# 5_CLOCK_GENERATOR.net
KiCad netlist of a schematic drawn in Altium Designer
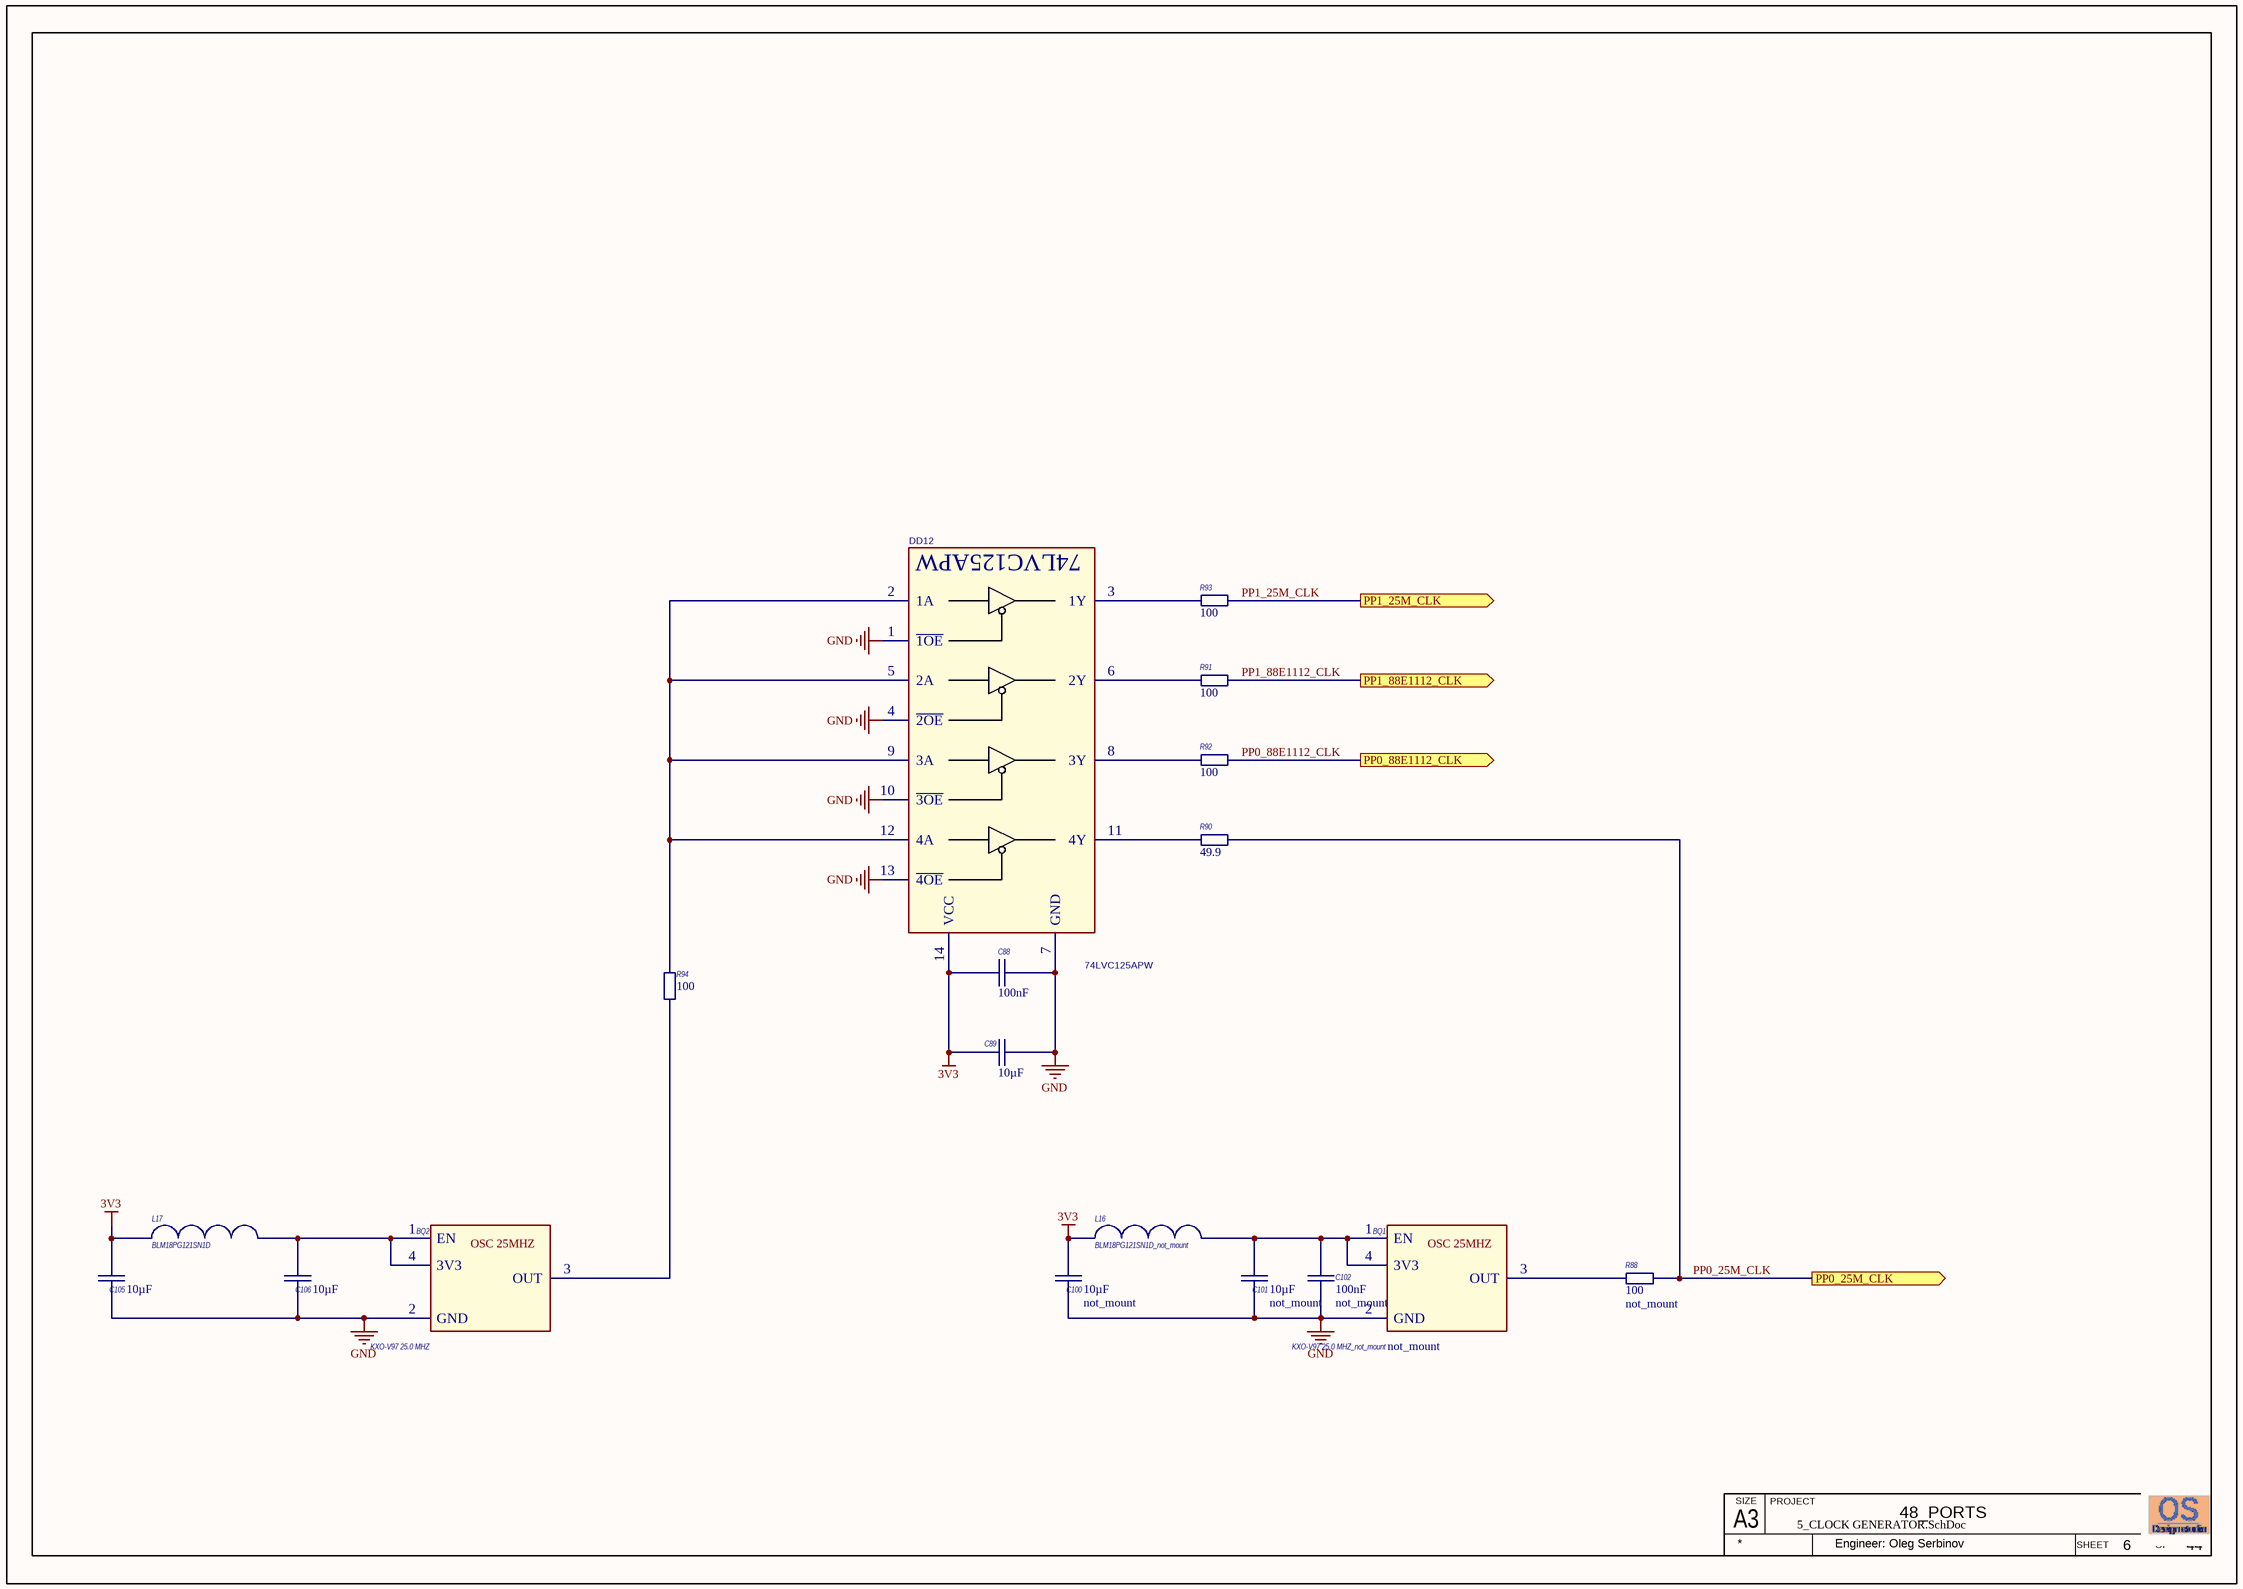
[diagram p0: 5_CLOCK GENERATOR.SchDoc]

(export (version "E")
  (design (tool "Eeschema 10.0.6"))
  (components
    (comp (ref "BQ1")
      (value "KXO-V97 25.0 MHZ_not_mount")
      (footprint "KXO-V97")
      (description "Oscillator 25MHZ 3.3V HCMOS SMT_not_mount")
      (fields
        (field (name "MANUFACTURER") "EYER ELECTRONIC")
        (field (name "MANUFACTURER PART NUMBER") "KXO-V97 25.0 MHZ")
        (field (name "NOTES") "not_mount")
      )
      (libsource (lib "CRYSTALS") (part "Oscillator 25MHZ 3.3V_not_mount"))
    )
    (comp (ref "BQ2")
      (value "KXO-V97 25.0 MHZ")
      (footprint "KXO-V97")
      (description "Oscillator 25MHZ 3.3V HCMOS SMT")
      (fields
        (field (name "MANUFACTURER") "EYER ELECTRONIC")
        (field (name "CUSTOMER PART NUMBER") "Генератор, Oscillator 25MHZ 3.3V HCMOS, 7050")
      )
      (libsource (lib "CRYSTALS") (part "Oscillator 25MHZ 3.3V"))
    )
    (comp (ref "C88")
      (value "GRM155R71E104KE14D")
      (footprint "C0402_IPC High Density")
      (description "C0402, 100nF, 25V, X7R")
      (fields
        (field (name "MANUFACTURER") "Murata")
        (field (name "CAPACITANCE") "100nF")
        (field (name "CUSTOMER PART NUMBER") "Конденсатор, 100n, 0402, 25V, X7R, 10%")
      )
      (libsource (lib "CAPACITORS") (part "GRM155R71E104KE14D"))
    )
    (comp (ref "C89")
      (value "GRM21BR61C106KE15")
      (footprint "CAPC2012[0805]")
      (description "C0805, 10uF 10%, 16V, X5R")
      (fields
        (field (name "MANUFACTURER") "Murata")
        (field (name "TOLERANCE") "±10%")
        (field (name "CAPACITANCE") "10µF")
      )
      (libsource (lib "CAPACITORS") (part "GRM21BR61C106KE15"))
    )
    (comp (ref "C100")
      (value "GRM21BR61C106KE15_not_mount")
      (footprint "CAPC2012[0805]")
      (description "C0805, 10uF 10%, 16V, X5R")
      (fields
        (field (name "MANUFACTURER") "Murata")
        (field (name "TOLERANCE") "±10%")
        (field (name "CAPACITANCE") "10µF")
        (field (name "NOTES") "not_mount")
      )
      (libsource (lib "CAPACITORS") (part "GRM21BR61C106KE15_not_mount"))
    )
    (comp (ref "C101")
      (value "GRM21BR61C106KE15_not_mount")
      (footprint "CAPC2012[0805]")
      (description "C0805, 10uF 10%, 16V, X5R")
      (fields
        (field (name "MANUFACTURER") "Murata")
        (field (name "TOLERANCE") "±10%")
        (field (name "CAPACITANCE") "10µF")
        (field (name "NOTES") "not_mount")
      )
      (libsource (lib "CAPACITORS") (part "GRM21BR61C106KE15_not_mount"))
    )
    (comp (ref "C102")
      (value "GRM155R71C104KA88_not_mount")
      (footprint "C0402_IPC High Density")
      (description "C0402, 100nF, 16V, X7R")
      (fields
        (field (name "MANUFACTURER") "Murata")
        (field (name "CAPACITANCE") "100nF")
        (field (name "RPART NUMBER") "CC0402KRX7R7BB104 ; CL05B104KO5NNNC ; C1005X7R1C104K050BC ; EMK105B7104KV-F ; C0402C104K4RAC7411")
        (field (name "NOTES") "not_mount")
      )
      (libsource (lib "CAPACITORS") (part "GRM155R71C104KA88_not_mount"))
    )
    (comp (ref "C105")
      (value "GRM21BR61C106KE15")
      (footprint "CAPC2012[0805]")
      (description "C0805, 10uF 10%, 16V, X5R")
      (fields
        (field (name "MANUFACTURER") "Murata")
        (field (name "TOLERANCE") "±10%")
        (field (name "CAPACITANCE") "10µF")
      )
      (libsource (lib "CAPACITORS") (part "GRM21BR61C106KE15"))
    )
    (comp (ref "C106")
      (value "GRM21BR61C106KE15")
      (footprint "CAPC2012[0805]")
      (description "C0805, 10uF 10%, 16V, X5R")
      (fields
        (field (name "MANUFACTURER") "Murata")
        (field (name "TOLERANCE") "±10%")
        (field (name "CAPACITANCE") "10µF")
      )
      (libsource (lib "CAPACITORS") (part "GRM21BR61C106KE15"))
    )
    (comp (ref "DD12")
      (value "74LVC125APW")
      (footprint "TSSOP-14")
      (description "IC BUFFERS 4 bit, 4 nS  TSSOP14")
      (fields
        (field (name "MANUFACTURER") "Texas Instruments")
        (field (name "MANUFACTURER PART NUMBER") "SN74LVC125APWR")
      )
      (libsource (lib "DIGITAL and ANALIG ICs") (part "74LVC125APW"))
    )
    (comp (ref "L16")
      (value "BLM18PG121SN1D_not_mount")
      (footprint "INDC1608X95N")
      (description "FILTER BLM18 (0603, 2A)_not_mount")
      (fields
        (field (name "MANUFACTURER") "MURATA")
        (field (name "MANUFACTURER PART NUMBER") "BLM18PG471SN1D")
      )
      (libsource (lib "INDUCTORS") (part "BLM18PG121SN1D_not_mount"))
    )
    (comp (ref "L17")
      (value "BLM18PG121SN1D")
      (footprint "INDC1608X95N")
      (description "FILTER BLM18 (0603, 2A)")
      (fields
        (field (name "MANUFACTURER") "Murata")
        (field (name "RPART NUMBER") "MPZ1608S121ATAH0 ; CIC10P121NC ; MPZ1608S121ATDH5 ; BLM18PG121SH1D ; 742792625")
      )
      (libsource (lib "INDUCTORS") (part "BLM18PG121SN1D"))
    )
    (comp (ref "R88")
      (value "ERJ-2RKF1000X_not_mount")
      (footprint "R0402_IPC High Density")
      (description "R0402, 100R 1%_not_mount")
      (fields
        (field (name "MANUFACTURER") "Panasonic")
        (field (name "TOLERANCE") "1 %")
        (field (name "RESISTANCE") "100")
        (field (name "NOTES") "not_mount")
      )
      (libsource (lib "RESISTOR") (part "ERJ-2RKF1000X_not_mount"))
    )
    (comp (ref "R90")
      (value "ERJ-2RKF49R9X")
      (footprint "R0402_IPC High Density")
      (description "R0402, 49.9R 1%")
      (fields
        (field (name "MANUFACTURER") "Panasonic")
        (field (name "TOLERANCE") "1 %")
        (field (name "RESISTANCE") "49.9")
      )
      (libsource (lib "RESISTOR") (part "ERJ-2RKF49R9X"))
    )
    (comp (ref "R91")
      (value "ERJ-2RKF1000X")
      (footprint "R0402_IPC High Density")
      (description "R0402, 100R 1%")
      (fields
        (field (name "MANUFACTURER") "Panasonic")
        (field (name "TOLERANCE") "1 %")
        (field (name "RESISTANCE") "100")
      )
      (libsource (lib "RESISTOR") (part "ERJ-2RKF1000X"))
    )
    (comp (ref "R92")
      (value "ERJ-2RKF1000X")
      (footprint "R0402_IPC High Density")
      (description "R0402, 100R 1%")
      (fields
        (field (name "MANUFACTURER") "Panasonic")
        (field (name "TOLERANCE") "1 %")
        (field (name "RESISTANCE") "100")
      )
      (libsource (lib "RESISTOR") (part "ERJ-2RKF1000X"))
    )
    (comp (ref "R93")
      (value "ERJ-2RKF1000X")
      (footprint "R0402_IPC High Density")
      (description "R0402, 100R 1%")
      (fields
        (field (name "MANUFACTURER") "Panasonic")
        (field (name "TOLERANCE") "1 %")
        (field (name "RESISTANCE") "100")
      )
      (libsource (lib "RESISTOR") (part "ERJ-2RKF1000X"))
    )
    (comp (ref "R94")
      (value "ERJ-2RKF1000X")
      (footprint "R0402_IPC High Density")
      (description "R0402, 100R 1%")
      (fields
        (field (name "MANUFACTURER") "Panasonic")
        (field (name "TOLERANCE") "1 %")
        (field (name "RESISTANCE") "100")
      )
      (libsource (lib "RESISTOR") (part "ERJ-2RKF1000X"))
    )
  )
  (nets
    (net (code "1") (name "/PP0_25M_CLK") (class "Default")
      (node (ref "R88") (pin "1") (pintype "passive"))
      (node (ref "R90") (pin "1") (pintype "passive"))
    )
    (net (code "2") (name "/PP0_88E1112_CLK") (class "Default")
      (node (ref "R92") (pin "1") (pintype "passive"))
    )
    (net (code "3") (name "/PP1_25M_CLK") (class "Default") (node (ref "R93") (pin "1") (pintype "passive")))
    (net (code "4") (name "/PP1_88E1112_CLK") (class "Default")
      (node (ref "R91") (pin "1") (pintype "passive"))
    )
    (net (code "5") (name "3V3") (class "Default")
      (node (ref "C100") (pin "1") (pintype "passive"))
      (node (ref "C105") (pin "1") (pintype "passive"))
      (node (ref "C88") (pin "1") (pintype "passive"))
      (node (ref "C89") (pin "1") (pintype "passive"))
      (node (ref "DD12") (pin "14") (pinfunction "VCC_14") (pintype "passive"))
      (node (ref "L16") (pin "1") (pinfunction "1_1") (pintype "passive"))
      (node (ref "L17") (pin "1") (pinfunction "1_1") (pintype "passive"))
    )
    (net (code "6") (name "GND") (class "Default")
      (node (ref "BQ1") (pin "2") (pinfunction "GND_2") (pintype "passive"))
      (node (ref "BQ2") (pin "2") (pinfunction "GND_2") (pintype "passive"))
      (node (ref "C100") (pin "2") (pintype "passive"))
      (node (ref "C101") (pin "2") (pintype "passive"))
      (node (ref "C102") (pin "1") (pintype "passive"))
      (node (ref "C105") (pin "2") (pintype "passive"))
      (node (ref "C106") (pin "2") (pintype "passive"))
      (node (ref "C88") (pin "2") (pintype "passive"))
      (node (ref "C89") (pin "2") (pintype "passive"))
      (node (ref "DD12") (pin "1") (pinfunction "1OE_1") (pintype "passive"))
      (node (ref "DD12") (pin "10") (pinfunction "3OE_10") (pintype "passive"))
      (node (ref "DD12") (pin "13") (pinfunction "4OE_13") (pintype "passive"))
      (node (ref "DD12") (pin "4") (pinfunction "2OE_4") (pintype "passive"))
      (node (ref "DD12") (pin "7") (pinfunction "GND_7") (pintype "passive"))
    )
    (net (code "7") (name "Net-(BQ1-3V3)") (class "Default")
      (node (ref "BQ1") (pin "1") (pinfunction "EN_1") (pintype "passive"))
      (node (ref "BQ1") (pin "4") (pinfunction "3V3_4") (pintype "passive"))
      (node (ref "C101") (pin "1") (pintype "passive"))
      (node (ref "C102") (pin "2") (pintype "passive"))
      (node (ref "L16") (pin "2") (pinfunction "2_2") (pintype "passive"))
    )
    (net (code "8") (name "Net-(BQ1-OUT)") (class "Default")
      (node (ref "BQ1") (pin "3") (pinfunction "OUT_3") (pintype "passive"))
      (node (ref "R88") (pin "2") (pintype "passive"))
    )
    (net (code "9") (name "Net-(BQ2-3V3)") (class "Default")
      (node (ref "BQ2") (pin "1") (pinfunction "EN_1") (pintype "passive"))
      (node (ref "BQ2") (pin "4") (pinfunction "3V3_4") (pintype "passive"))
      (node (ref "C106") (pin "1") (pintype "passive"))
      (node (ref "L17") (pin "2") (pinfunction "2_2") (pintype "passive"))
    )
    (net (code "10") (name "Net-(BQ2-OUT)") (class "Default")
      (node (ref "BQ2") (pin "3") (pinfunction "OUT_3") (pintype "passive"))
      (node (ref "R94") (pin "2") (pintype "passive"))
    )
    (net (code "11") (name "Net-(DD12-1A)") (class "Default")
      (node (ref "DD12") (pin "12") (pinfunction "4A_12") (pintype "passive"))
      (node (ref "DD12") (pin "2") (pinfunction "1A_2") (pintype "passive"))
      (node (ref "DD12") (pin "5") (pinfunction "2A_5") (pintype "passive"))
      (node (ref "DD12") (pin "9") (pinfunction "3A_9") (pintype "passive"))
      (node (ref "R94") (pin "1") (pintype "passive"))
    )
    (net (code "12") (name "Net-(DD12-1Y)") (class "Default")
      (node (ref "DD12") (pin "3") (pinfunction "1Y_3") (pintype "passive"))
      (node (ref "R93") (pin "2") (pintype "passive"))
    )
    (net (code "13") (name "Net-(DD12-2Y)") (class "Default")
      (node (ref "DD12") (pin "6") (pinfunction "2Y_6") (pintype "passive"))
      (node (ref "R91") (pin "2") (pintype "passive"))
    )
    (net (code "14") (name "Net-(DD12-3Y)") (class "Default")
      (node (ref "DD12") (pin "8") (pinfunction "3Y_8") (pintype "passive"))
      (node (ref "R92") (pin "2") (pintype "passive"))
    )
    (net (code "15") (name "Net-(DD12-4Y)") (class "Default")
      (node (ref "DD12") (pin "11") (pinfunction "4Y_11") (pintype "passive"))
      (node (ref "R90") (pin "2") (pintype "passive"))
    )
  )
)
